# network_board.net
KiCad netlist of a schematic drawn in EAGLE
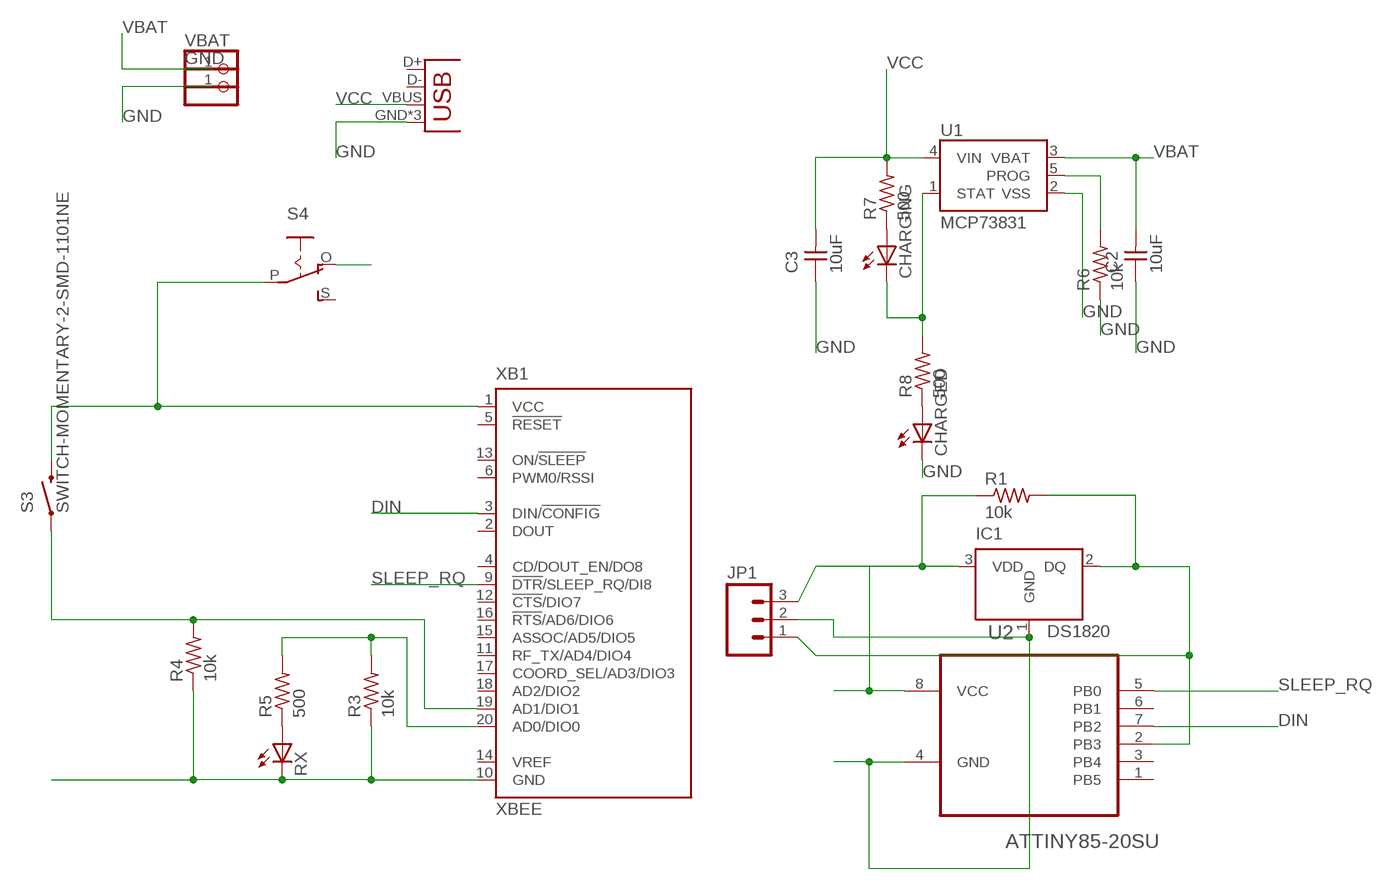
[diagram p0: schematic, sheet 1]

(export (version "E")
  (design (tool "Eeschema 10.0.6"))
  (components
    (comp (ref "C2")
      (value "10uF")
      (footprint "eagle-import:1206")
      (libsource (lib "eagle-import") (part "UNPOLARIZED_CAPACITOR1206"))
    )
    (comp (ref "C3")
      (value "10uF")
      (footprint "eagle-import:1206")
      (libsource (lib "eagle-import") (part "UNPOLARIZED_CAPACITOR1206"))
    )
    (comp (ref "CHARGED")
      (value "LED1206")
      (footprint "eagle-import:1206")
      (libsource (lib "eagle-import") (part "LED1206"))
    )
    (comp (ref "CHARGING")
      (value "LED1206")
      (footprint "eagle-import:1206")
      (libsource (lib "eagle-import") (part "LED1206"))
    )
    (comp (ref "GND")
      (value "PINHD-1X1CB")
      (footprint "eagle-import:1X01-CLEANBIG")
      (libsource (lib "eagle-import") (part "PINHD-1X1CB"))
    )
    (comp (ref "IC1")
      (value "DS1820")
      (footprint "eagle-import:TO-92")
      (libsource (lib "eagle-import") (part "DS1820"))
    )
    (comp (ref "JP1")
      (value "M03PTH")
      (footprint "eagle-import:1X03")
      (libsource (lib "eagle-import") (part "M03PTH"))
    )
    (comp (ref "R1")
      (value "10k")
      (footprint "eagle-import:1206")
      (libsource (lib "eagle-import") (part "RESISTOR1206"))
    )
    (comp (ref "R3")
      (value "10k")
      (footprint "eagle-import:R1206")
      (libsource (lib "eagle-import") (part "RES-US1206"))
    )
    (comp (ref "R4")
      (value "10k")
      (footprint "eagle-import:R1206")
      (libsource (lib "eagle-import") (part "RES-US1206"))
    )
    (comp (ref "R5")
      (value "500")
      (footprint "eagle-import:R1206")
      (libsource (lib "eagle-import") (part "RES-US1206"))
    )
    (comp (ref "R6")
      (value "10k")
      (footprint "eagle-import:R1206")
      (libsource (lib "eagle-import") (part "RES-US1206"))
    )
    (comp (ref "R7")
      (value "500")
      (footprint "eagle-import:R1206")
      (libsource (lib "eagle-import") (part "RES-US1206"))
    )
    (comp (ref "R8")
      (value "500")
      (footprint "eagle-import:R1206")
      (libsource (lib "eagle-import") (part "RES-US1206"))
    )
    (comp (ref "RX")
      (value "LED1206")
      (footprint "eagle-import:1206")
      (libsource (lib "eagle-import") (part "LED1206"))
    )
    (comp (ref "S3")
      (value "SWITCH-MOMENTARY-2-SMD-1101NE")
      (footprint "eagle-import:TACTILE-SWITCH-1101NE")
      (libsource (lib "eagle-import") (part "SWITCH-MOMENTARY-2-SMD-1101NE"))
    )
    (comp (ref "S4")
      (value "EG1218S")
      (footprint "eagle-import:EG1218")
      (libsource (lib "eagle-import") (part "EG1218S"))
    )
    (comp (ref "U1")
      (value "MCP73831")
      (footprint "eagle-import:SOT23-5")
      (libsource (lib "eagle-import") (part "MCP73831"))
    )
    (comp (ref "U2")
      (value "ATTINY85-20SU")
      (footprint "eagle-import:SOIC127P798X216-8N")
      (libsource (lib "eagle-import") (part "ATTINY85-20SU"))
    )
    (comp (ref "VBAT")
      (value "PINHD-1X1CB")
      (footprint "eagle-import:1X01-CLEANBIG")
      (libsource (lib "eagle-import") (part "PINHD-1X1CB"))
    )
    (comp (ref "X1")
      (value "USB-MICROB")
      (footprint "eagle-import:USB-MICROB")
      (libsource (lib "eagle-import") (part "USB-MICROB"))
    )
    (comp (ref "XB1")
      (value "XBEE")
      (footprint "eagle-import:XBEE")
      (fields (field (name "MPN") "XBP24-Z7UIT-004"))
      (libsource (lib "eagle-import") (part "XBEE"))
    )
  )
  (nets
    (net (code "1") (name "/DIN") (class "Default")
      (node (ref "U2") (pin "7") (pinfunction "PB2_7") (pintype "bidirectional"))
      (node (ref "XB1") (pin "3") (pinfunction "DIN/~{CONFIG}_3") (pintype "input"))
    )
    (net (code "2") (name "/GND") (class "Default")
      (node (ref "C2") (pin "1") (pinfunction "1_1") (pintype "passive"))
      (node (ref "C3") (pin "1") (pinfunction "1_1") (pintype "passive"))
      (node (ref "CHARGED") (pin "2") (pinfunction "C_2") (pintype "passive"))
      (node (ref "GND") (pin "1") (pinfunction "1_1") (pintype "passive"))
      (node (ref "IC1") (pin "1") (pinfunction "GND_1") (pintype "power_in"))
      (node (ref "JP1") (pin "2") (pinfunction "2_2") (pintype "passive"))
      (node (ref "R3") (pin "1") (pinfunction "1_1") (pintype "passive"))
      (node (ref "R4") (pin "1") (pinfunction "1_1") (pintype "passive"))
      (node (ref "R6") (pin "1") (pinfunction "1_1") (pintype "passive"))
      (node (ref "RX") (pin "2") (pinfunction "C_2") (pintype "passive"))
      (node (ref "U1") (pin "2") (pinfunction "VSS_2") (pintype "power_in"))
      (node (ref "U2") (pin "4") (pinfunction "GND_4") (pintype "passive"))
      (node (ref "X1") (pin "GND") (pinfunction "GND_GND") (pintype "bidirectional"))
      (node (ref "X1") (pin "MT1") (pinfunction "GND_MT1") (pintype "bidirectional"))
      (node (ref "X1") (pin "MT2") (pinfunction "GND_MT2") (pintype "bidirectional"))
      (node (ref "XB1") (pin "10") (pinfunction "GND_10") (pintype "power_in"))
    )
    (net (code "3") (name "/SLEEP_RQ") (class "Default")
      (node (ref "U2") (pin "5") (pinfunction "PB0_5") (pintype "bidirectional"))
      (node (ref "XB1") (pin "9") (pinfunction "~{DTR}/SLEEP_RQ/DI8_9") (pintype "bidirectional"))
    )
    (net (code "4") (name "/VBAT") (class "Default")
      (node (ref "C2") (pin "2") (pinfunction "2_2") (pintype "passive"))
      (node (ref "S4") (pin "O") (pinfunction "O_O") (pintype "passive"))
      (node (ref "U1") (pin "3") (pinfunction "VBAT_3") (pintype "power_in"))
      (node (ref "VBAT") (pin "1") (pinfunction "1_1") (pintype "passive"))
    )
    (net (code "5") (name "/VCC") (class "Default")
      (node (ref "C3") (pin "2") (pinfunction "2_2") (pintype "passive"))
      (node (ref "R7") (pin "2") (pinfunction "2_2") (pintype "passive"))
      (node (ref "U1") (pin "4") (pinfunction "VIN_4") (pintype "power_in"))
      (node (ref "X1") (pin "VBUS") (pinfunction "VBUS_VBUS") (pintype "bidirectional"))
    )
    (net (code "6") (name "/VIN") (class "Default")
      (node (ref "IC1") (pin "3") (pinfunction "VDD_3") (pintype "input"))
      (node (ref "JP1") (pin "3") (pinfunction "3_3") (pintype "passive"))
      (node (ref "R1") (pin "1") (pinfunction "1_1") (pintype "passive"))
      (node (ref "S3") (pin "P$2") (pinfunction "2_P$2") (pintype "passive"))
      (node (ref "S4") (pin "P") (pinfunction "P_P") (pintype "passive"))
      (node (ref "U2") (pin "8") (pinfunction "VCC_8") (pintype "power_in"))
      (node (ref "XB1") (pin "1") (pinfunction "VCC_1") (pintype "power_in"))
    )
    (net (code "7") (name "Net-(CHARGED-A)") (class "Default")
      (node (ref "CHARGED") (pin "1") (pinfunction "A_1") (pintype "passive"))
      (node (ref "R8") (pin "1") (pinfunction "1_1") (pintype "passive"))
    )
    (net (code "8") (name "Net-(CHARGING-A)") (class "Default")
      (node (ref "CHARGING") (pin "1") (pinfunction "A_1") (pintype "passive"))
      (node (ref "R7") (pin "1") (pinfunction "1_1") (pintype "passive"))
    )
    (net (code "9") (name "Net-(CHARGING-C)") (class "Default")
      (node (ref "CHARGING") (pin "2") (pinfunction "C_2") (pintype "passive"))
      (node (ref "R8") (pin "2") (pinfunction "2_2") (pintype "passive"))
      (node (ref "U1") (pin "1") (pinfunction "STAT_1") (pintype "output"))
    )
    (net (code "10") (name "Net-(IC1-DQ)") (class "Default")
      (node (ref "IC1") (pin "2") (pinfunction "DQ_2") (pintype "output"))
      (node (ref "JP1") (pin "1") (pinfunction "1_1") (pintype "passive"))
      (node (ref "R1") (pin "2") (pinfunction "2_2") (pintype "passive"))
      (node (ref "U2") (pin "2") (pinfunction "PB3_2") (pintype "bidirectional"))
    )
    (net (code "11") (name "Net-(RX-A)") (class "Default")
      (node (ref "R5") (pin "1") (pinfunction "1_1") (pintype "passive"))
      (node (ref "RX") (pin "1") (pinfunction "A_1") (pintype "passive"))
    )
    (net (code "12") (name "Net-(S3-1)") (class "Default")
      (node (ref "R4") (pin "2") (pinfunction "2_2") (pintype "passive"))
      (node (ref "S3") (pin "P$1") (pinfunction "1_P$1") (pintype "passive"))
      (node (ref "XB1") (pin "19") (pinfunction "AD1/DIO1_19") (pintype "bidirectional"))
    )
    (net (code "13") (name "Net-(U1-PROG)") (class "Default")
      (node (ref "R6") (pin "2") (pinfunction "2_2") (pintype "passive"))
      (node (ref "U1") (pin "5") (pinfunction "PROG_5") (pintype "input"))
    )
    (net (code "14") (name "Net-(XB1-AD0{slash}DIO0)") (class "Default")
      (node (ref "R3") (pin "2") (pinfunction "2_2") (pintype "passive"))
      (node (ref "R5") (pin "2") (pinfunction "2_2") (pintype "passive"))
      (node (ref "XB1") (pin "20") (pinfunction "AD0/DIO0_20") (pintype "bidirectional"))
    )
    (net (code "15") (name "unconnected-(S4-PadS)") (class "Default")
      (node (ref "S4") (pin "S") (pinfunction "S_S") (pintype "passive"))
    )
    (net (code "16") (name "unconnected-(U2-PB1-Pad6)") (class "Default")
      (node (ref "U2") (pin "6") (pinfunction "PB1_6") (pintype "bidirectional"))
    )
    (net (code "17") (name "unconnected-(U2-PB4-Pad3)") (class "Default")
      (node (ref "U2") (pin "3") (pinfunction "PB4_3") (pintype "bidirectional"))
    )
    (net (code "18") (name "unconnected-(U2-PB5-Pad1)") (class "Default")
      (node (ref "U2") (pin "1") (pinfunction "PB5_1") (pintype "bidirectional"))
    )
    (net (code "19") (name "unconnected-(X1-PadD+)") (class "Default")
      (node (ref "X1") (pin "D+") (pinfunction "D+_D+") (pintype "bidirectional"))
    )
    (net (code "20") (name "unconnected-(X1-PadD-)") (class "Default")
      (node (ref "X1") (pin "D-") (pinfunction "D-_D-") (pintype "bidirectional"))
    )
    (net (code "21") (name "unconnected-(XB1-AD2{slash}DIO2-Pad18)") (class "Default")
      (node (ref "XB1") (pin "18") (pinfunction "AD2/DIO2_18") (pintype "bidirectional"))
    )
    (net (code "22") (name "unconnected-(XB1-ASSOC{slash}AD5{slash}DIO5-Pad15)") (class "Default")
      (node (ref "XB1") (pin "15") (pinfunction "ASSOC/AD5/DIO5_15") (pintype "bidirectional"))
    )
    (net (code "23") (name "unconnected-(XB1-CD{slash}DOUT_EN{slash}DO8-Pad4)") (class "Default")
      (node (ref "XB1") (pin "4") (pinfunction "CD/DOUT_EN/DO8_4") (pintype "output"))
    )
    (net (code "24") (name "unconnected-(XB1-COORD_SEL{slash}AD3{slash}DIO3-Pad17)") (class "Default")
      (node (ref "XB1") (pin "17") (pinfunction "COORD_SEL/AD3/DIO3_17") (pintype "bidirectional"))
    )
    (net (code "25") (name "unconnected-(XB1-DOUT-Pad2)") (class "Default")
      (node (ref "XB1") (pin "2") (pinfunction "DOUT_2") (pintype "output"))
    )
    (net (code "26") (name "unconnected-(XB1-ON{slash}~{SLEEP}-Pad13)") (class "Default")
      (node (ref "XB1") (pin "13") (pinfunction "ON/~{SLEEP}_13") (pintype "output"))
    )
    (net (code "27") (name "unconnected-(XB1-PWM0{slash}RSSI-Pad6)") (class "Default")
      (node (ref "XB1") (pin "6") (pinfunction "PWM0/RSSI_6") (pintype "output"))
    )
    (net (code "28") (name "unconnected-(XB1-RF_TX{slash}AD4{slash}DIO4-Pad11)") (class "Default")
      (node (ref "XB1") (pin "11") (pinfunction "RF_TX/AD4/DIO4_11") (pintype "bidirectional"))
    )
    (net (code "29") (name "unconnected-(XB1-VREF-Pad14)") (class "Default")
      (node (ref "XB1") (pin "14") (pinfunction "VREF_14") (pintype "input"))
    )
    (net (code "30") (name "unconnected-(XB1-~{CTS}{slash}DIO7-Pad12)") (class "Default")
      (node (ref "XB1") (pin "12") (pinfunction "~{CTS}/DIO7_12") (pintype "bidirectional"))
    )
    (net (code "31") (name "unconnected-(XB1-~{RESET}-Pad5)") (class "Default")
      (node (ref "XB1") (pin "5") (pinfunction "~{RESET}_5") (pintype "input"))
    )
    (net (code "32") (name "unconnected-(XB1-~{RTS}{slash}AD6{slash}DIO6-Pad16)") (class "Default")
      (node (ref "XB1") (pin "16") (pinfunction "~{RTS}/AD6/DIO6_16") (pintype "bidirectional"))
    )
  )
)
